# DALI.net
KiCad netlist of a schematic drawn in Altium Designer
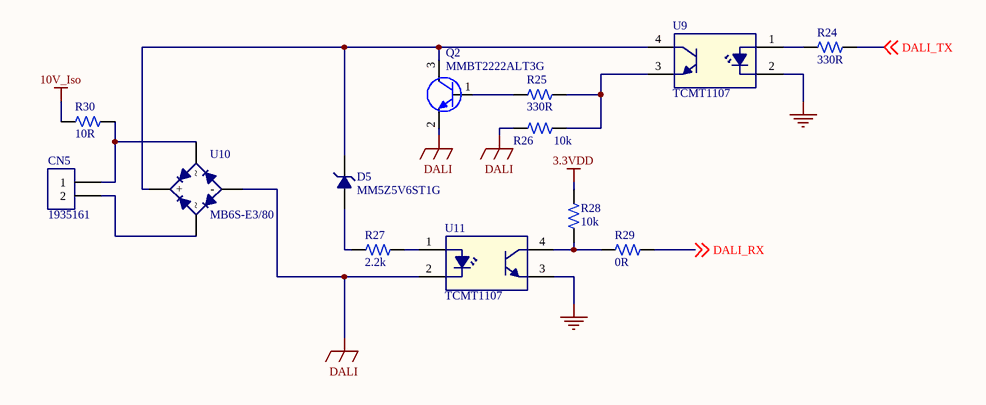
[diagram p0: DALI.SchDoc]

(export (version "E")
  (design (tool "Eeschema 10.0.6"))
  (components
    (comp (ref "CN5")
      (value "1935161")
      (footprint "TERM BLOCK PCB 2POS 5.0MM")
      (description "TERM BLOCK PCB 2POS 5.0MM")
      (fields (field (name "USER") "Rodrigo Balbi"))
      (libsource (lib "Conectores") (part "1935161  TERM BLOCK PCB 2X1"))
    )
    (comp (ref "D5")
      (value "MM5Z5V6ST1G")
      (footprint "SOD-523-3D")
      (description "DIODE ZENER 5.61V 500MW SOD523")
      (fields (field (name "USER") "Larissa"))
      (libsource (lib "Diodos") (part "MM5Z5V6ST1G DIODE ZENER 5.61V 500MW"))
    )
    (comp (ref "Q2")
      (value "MMBT2222ALT3G")
      (footprint "SOT23-3D")
      (description "TRANS NPN 40V 0.6A SOT-23")
      (fields (field (name "USER") "Larissa"))
      (libsource (lib "Transistores") (part "MMBT2222ALT3G TRANS NPN SOT23"))
    )
    (comp (ref "R24")
      (value "330R")
      (footprint "0603-3D")
      (description "RES SMD 330 OHM 5% 1/10W 0603")
      (fields (field (name "TOLERANCE") "5%") (field (name "USER") "Luiz F Siecola"))
      (libsource (lib "ResitoresPrjLib") (part "330R 5% 0603 TKF 1/10W"))
    )
    (comp (ref "R25")
      (value "330R")
      (footprint "0603-3D")
      (description "RES SMD 330 OHM 5% 1/10W 0603")
      (fields (field (name "TOLERANCE") "5%") (field (name "USER") "Luiz F Siecola"))
      (libsource (lib "ResitoresPrjLib") (part "330R 5% 0603 TKF 1/10W"))
    )
    (comp (ref "R26")
      (value "10k")
      (footprint "0603-3D")
      (description "RES SMD 10K OHM 1% 1/10W 0603")
      (fields
        (field (name "MANUFACTURER") "Yageo")
        (field (name "MANUFACTURER PART NUMBER") "RC0603FR-0710KL")
        (field (name "USER") "Pedro Vilela")
      )
      (libsource (lib "ResitoresPrjLib") (part "10k 1% 0603 TNF 1/10W"))
    )
    (comp (ref "R27")
      (value "2.2k")
      (footprint "0603-3D")
      (description "RES SMD 2.2K OHM 5% 1/10W 0603")
      (fields (field (name "TOLERANCE") "5%") (field (name "USER") "Rodrigo Balbi"))
      (libsource (lib "ResitoresPrjLib") (part "2.2k 5% 0603 TKF 1/10W"))
    )
    (comp (ref "R28")
      (value "10k")
      (footprint "0603-3D")
      (description "RES SMD 10K OHM 1% 1/10W 0603")
      (fields
        (field (name "MANUFACTURER") "Yageo")
        (field (name "MANUFACTURER PART NUMBER") "RC0603FR-0710KL")
        (field (name "USER") "Pedro Vilela")
      )
      (libsource (lib "ResitoresPrjLib") (part "10k 1% 0603 TNF 1/10W"))
    )
    (comp (ref "R29")
      (value "0R")
      (footprint "0603-3D")
      (description "RES SMD 0.0OHM JUMPER 1/10W 0603")
      (fields (field (name "USER") "Reis"))
      (libsource (lib "ResitoresPrjLib") (part "0R 0603 TKF 1/10W"))
    )
    (comp (ref "R30")
      (value "10R")
      (footprint "0603-3D")
      (description "RES SMD 10 OHM 5% 1/10W 0603")
      (fields (field (name "TOLERANCE") "5%") (field (name "USER") "Rodrigo Villela"))
      (libsource (lib "ResitoresPrjLib") (part "10R 5% 0603 TKF 1/10W"))
    )
    (comp (ref "U9")
      (value "TCMT1107")
      (footprint "SOP4")
      (description "OPTOISOLATOR 3.75KV TRANS 4-SOP")
      (fields (field (name "USER") "Jean Pierre"))
      (libsource (lib "Opticos") (part "TCMT1107 OPTO TRANS"))
    )
    (comp (ref "U10")
      (value "MB6S-E3/80")
      (footprint "TO-269AA-3D")
      (description "Bridge Rectifier Single Phase 600V 500mA Surface Mount TO-269AA (MBS)")
      (fields (field (name "USER") "Reis"))
      (libsource (lib "Diodos") (part "MB6S-E3/80 BRIDGE RECTIFIER SINGLE"))
    )
    (comp (ref "U11")
      (value "TCMT1107")
      (footprint "SOP4")
      (description "OPTOISOLATOR 3.75KV TRANS 4-SOP")
      (fields (field (name "USER") "Jean Pierre"))
      (libsource (lib "") (part "TCMT1107 OPTO TRANS_1"))
    )
  )
  (nets
    (net (code "1") (name "3.3VDD") (class "Default")
      (node (ref "R28") (pin "1") (pinfunction "1_1") (pintype "passive"))
    )
    (net (code "2") (name "10V_Iso") (class "Default")
      (node (ref "R30") (pin "1") (pinfunction "1_1") (pintype "passive"))
    )
    (net (code "3") (name "DALI") (class "Default")
      (node (ref "Q2") (pin "2") (pinfunction "E_2") (pintype "passive"))
      (node (ref "R26") (pin "2") (pinfunction "2_2") (pintype "passive"))
      (node (ref "U10") (pin "4") (pinfunction "-_4") (pintype "passive"))
      (node (ref "U11") (pin "2") (pinfunction "K_2") (pintype "passive"))
    )
    (net (code "4") (name "DALI_RX") (class "Default")
      (node (ref "R29") (pin "2") (pinfunction "2_2") (pintype "passive"))
    )
    (net (code "5") (name "DALI_TX") (class "Default")
      (node (ref "R24") (pin "2") (pinfunction "2_2") (pintype "passive"))
    )
    (net (code "6") (name "GND") (class "Default")
      (node (ref "U11") (pin "3") (pinfunction "E_3") (pintype "passive"))
      (node (ref "U9") (pin "2") (pinfunction "K_2") (pintype "passive"))
    )
    (net (code "7") (name "Net-(CN5-Pad1)") (class "Default")
      (node (ref "CN5") (pin "1") (pinfunction "1_1") (pintype "passive"))
      (node (ref "R30") (pin "2") (pinfunction "2_2") (pintype "passive"))
      (node (ref "U10") (pin "2") (pinfunction "~_2") (pintype "passive"))
    )
    (net (code "8") (name "Net-(CN5-Pad2)") (class "Default")
      (node (ref "CN5") (pin "2") (pinfunction "2_2") (pintype "passive"))
      (node (ref "U10") (pin "1") (pinfunction "~_1") (pintype "passive"))
    )
    (net (code "9") (name "Net-(D5-Pad1)") (class "Default")
      (node (ref "D5") (pin "1") (pinfunction "1_1") (pintype "passive"))
      (node (ref "R27") (pin "2") (pinfunction "2_2") (pintype "passive"))
    )
    (net (code "10") (name "Net-(Q2-B)") (class "Default")
      (node (ref "Q2") (pin "1") (pinfunction "B_1") (pintype "passive"))
      (node (ref "R25") (pin "1") (pinfunction "1_1") (pintype "passive"))
    )
    (net (code "11") (name "Net-(Q2-C)") (class "Default")
      (node (ref "D5") (pin "2") (pinfunction "2_2") (pintype "passive"))
      (node (ref "Q2") (pin "3") (pinfunction "C_3") (pintype "passive"))
      (node (ref "U10") (pin "3") (pinfunction "+_3") (pintype "passive"))
      (node (ref "U9") (pin "4") (pinfunction "C_4") (pintype "passive"))
    )
    (net (code "12") (name "Net-(U9-A)") (class "Default")
      (node (ref "R24") (pin "1") (pinfunction "1_1") (pintype "passive"))
      (node (ref "U9") (pin "1") (pinfunction "A_1") (pintype "passive"))
    )
    (net (code "13") (name "Net-(U9-E)") (class "Default")
      (node (ref "R25") (pin "2") (pinfunction "2_2") (pintype "passive"))
      (node (ref "R26") (pin "1") (pinfunction "1_1") (pintype "passive"))
      (node (ref "U9") (pin "3") (pinfunction "E_3") (pintype "passive"))
    )
    (net (code "14") (name "Net-(U11-A)") (class "Default")
      (node (ref "R27") (pin "1") (pinfunction "1_1") (pintype "passive"))
      (node (ref "U11") (pin "1") (pinfunction "A_1") (pintype "passive"))
    )
    (net (code "15") (name "Net-(U11-C)") (class "Default")
      (node (ref "R28") (pin "2") (pinfunction "2_2") (pintype "passive"))
      (node (ref "R29") (pin "1") (pinfunction "1_1") (pintype "passive"))
      (node (ref "U11") (pin "4") (pinfunction "C_4") (pintype "passive"))
    )
  )
)
